# AMP.net
KiCad netlist of a schematic drawn in Altium Designer
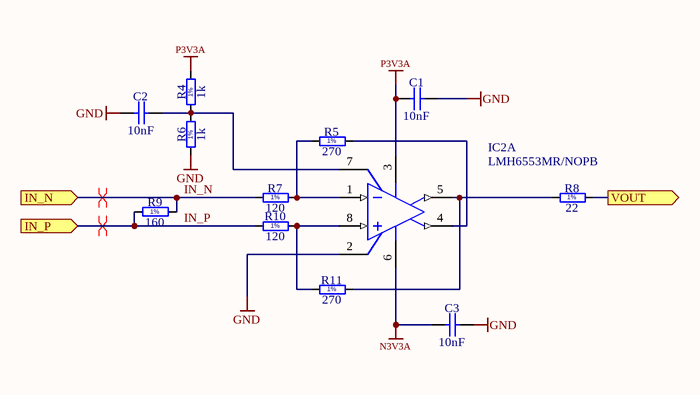
[diagram p0: AMP.SchDoc]

(export (version "E")
  (design (tool "Eeschema 10.0.6"))
  (components
    (comp (ref "C1")
      (value "10nF")
      (footprint "CAPC1608X87N")
      (description "Non-polarised capacitor")
      (fields
        (field (name "PART NUMBER") "CC0603_10NF_50V_10%_X7R")
        (field (name "VOLTAGE") "50V")
        (field (name "AUTHOR") "CERN DEM JLC")
      )
      (libsource (lib "Capacitors") (part "Capacitor - non polarized"))
    )
    (comp (ref "C2")
      (value "10nF")
      (footprint "CAPC1608X87N")
      (description "Non-polarised capacitor")
      (fields
        (field (name "PART NUMBER") "CC0603_10NF_50V_10%_X7R")
        (field (name "VOLTAGE") "50V")
        (field (name "AUTHOR") "CERN DEM JLC")
      )
      (libsource (lib "Capacitors") (part "Capacitor - non polarized"))
    )
    (comp (ref "C3")
      (value "10nF")
      (footprint "CAPC1608X87N")
      (description "Non-polarised capacitor")
      (fields
        (field (name "PART NUMBER") "CC0603_10NF_50V_10%_X7R")
        (field (name "VOLTAGE") "50V")
        (field (name "AUTHOR") "CERN DEM JLC")
      )
      (libsource (lib "Capacitors") (part "Capacitor - non polarized"))
    )
    (comp (ref "IC2")
      (value "LMH6553MR/NOPB")
      (footprint "DDA0008D_M")
      (description "900 MHz Fully Differential Amplifier with Output Limiting Clamp, 8-pin PSOP, Pb-Free")
      (fields (field (name "MANUFACTURER") "Texas Instruments"))
      (libsource (lib "Altium Content Vault") (part "AMP-DIFA-LMH6553-9"))
    )
    (comp (ref "R4")
      (value "1k")
      (footprint "RESC1608X55N")
      (description "Resistor - 1%")
      (fields
        (field (name "PART NUMBER") "R0603_1K_1%_0.1W_100PPM")
        (field (name "POWER") "0.1W")
        (field (name "AUTHOR") "CERN DEM JLC")
      )
      (libsource (lib "Resistors") (part "Resistor - 1%"))
    )
    (comp (ref "R5")
      (value "270")
      (footprint "RESC1608X55N")
      (description "Resistor - 1%")
      (fields
        (field (name "PART NUMBER") "R0603_270R_1%_0.1W_100PPM")
        (field (name "POWER") "0.1W")
        (field (name "AUTHOR") "CERN DEM JLC")
      )
      (libsource (lib "Resistors") (part "Resistor - 1%"))
    )
    (comp (ref "R6")
      (value "1k")
      (footprint "RESC1608X55N")
      (description "Resistor - 1%")
      (fields
        (field (name "PART NUMBER") "R0603_1K_1%_0.1W_100PPM")
        (field (name "POWER") "0.1W")
        (field (name "AUTHOR") "CERN DEM JLC")
      )
      (libsource (lib "Resistors") (part "Resistor - 1%"))
    )
    (comp (ref "R7")
      (value "120")
      (footprint "RESC1608X55N")
      (description "Resistor - 1%")
      (fields
        (field (name "PART NUMBER") "R0603_120R_1%_0.1W_100PPM")
        (field (name "POWER") "0.1W")
        (field (name "AUTHOR") "CERN DEM JLC")
      )
      (libsource (lib "Resistors") (part "Resistor - 1%"))
    )
    (comp (ref "R8")
      (value "22")
      (footprint "RESC1608X55N")
      (description "Resistor - 1%")
      (fields
        (field (name "PART NUMBER") "R0603_22R_1%_0.1W_100PPM")
        (field (name "POWER") "0.1W")
        (field (name "AUTHOR") "CERN DEM JLC")
      )
      (libsource (lib "Resistors") (part "Resistor - 1%"))
    )
    (comp (ref "R9")
      (value "160")
      (footprint "RESC1608X55N")
      (description "Resistor - 1%")
      (fields
        (field (name "PART NUMBER") "R0603_160R_1%_0.1W_100PPM")
        (field (name "POWER") "0.1W")
        (field (name "AUTHOR") "CERN DEM JLC")
      )
      (libsource (lib "Resistors") (part "Resistor - 1%"))
    )
    (comp (ref "R10")
      (value "120")
      (footprint "RESC1608X55N")
      (description "Resistor - 1%")
      (fields
        (field (name "PART NUMBER") "R0603_120R_1%_0.1W_100PPM")
        (field (name "POWER") "0.1W")
        (field (name "AUTHOR") "CERN DEM JLC")
      )
      (libsource (lib "Resistors") (part "Resistor - 1%"))
    )
    (comp (ref "R11")
      (value "270")
      (footprint "RESC1608X55N")
      (description "Resistor - 1%")
      (fields
        (field (name "PART NUMBER") "R0603_270R_1%_0.1W_100PPM")
        (field (name "POWER") "0.1W")
        (field (name "AUTHOR") "CERN DEM JLC")
      )
      (libsource (lib "Resistors") (part "Resistor - 1%"))
    )
  )
  (nets
    (net (code "1") (name "/IN_N") (class "Default")
      (node (ref "R7") (pin "1") (pinfunction "1_1") (pintype "passive"))
      (node (ref "R9") (pin "2") (pinfunction "2_2") (pintype "passive"))
    )
    (net (code "2") (name "/IN_P") (class "Default")
      (node (ref "R10") (pin "1") (pinfunction "1_1") (pintype "passive"))
      (node (ref "R9") (pin "1") (pinfunction "1_1") (pintype "passive"))
    )
    (net (code "3") (name "/VOUT") (class "Default")
      (node (ref "R8") (pin "2") (pinfunction "2_2") (pintype "passive"))
    )
    (net (code "4") (name "GND") (class "Default")
      (node (ref "C1") (pin "2") (pinfunction "2_2") (pintype "passive"))
      (node (ref "C2") (pin "1") (pinfunction "1_1") (pintype "passive"))
      (node (ref "C3") (pin "2") (pinfunction "2_2") (pintype "passive"))
      (node (ref "IC2") (pin "2") (pinfunction "VCM_2") (pintype "passive"))
      (node (ref "R6") (pin "1") (pinfunction "1_1") (pintype "passive"))
    )
    (net (code "5") (name "N3V3A") (class "Default")
      (node (ref "C3") (pin "1") (pinfunction "1_1") (pintype "passive"))
      (node (ref "IC2") (pin "6") (pinfunction "V-_6") (pintype "power_in"))
    )
    (net (code "6") (name "Net-(IC2A-IN+)") (class "Default")
      (node (ref "IC2") (pin "8") (pinfunction "IN+_8") (pintype "input"))
      (node (ref "R10") (pin "2") (pinfunction "2_2") (pintype "passive"))
      (node (ref "R11") (pin "1") (pinfunction "1_1") (pintype "passive"))
    )
    (net (code "7") (name "Net-(IC2A-IN-)") (class "Default")
      (node (ref "IC2") (pin "1") (pinfunction "IN-_1") (pintype "input"))
      (node (ref "R5") (pin "1") (pinfunction "1_1") (pintype "passive"))
      (node (ref "R7") (pin "2") (pinfunction "2_2") (pintype "passive"))
    )
    (net (code "8") (name "Net-(IC2A-OUT+)") (class "Default")
      (node (ref "IC2") (pin "4") (pinfunction "OUT+_4") (pintype "output"))
      (node (ref "R5") (pin "2") (pinfunction "2_2") (pintype "passive"))
    )
    (net (code "9") (name "Net-(IC2A-OUT-)") (class "Default")
      (node (ref "IC2") (pin "5") (pinfunction "OUT-_5") (pintype "output"))
      (node (ref "R11") (pin "2") (pinfunction "2_2") (pintype "passive"))
      (node (ref "R8") (pin "1") (pinfunction "1_1") (pintype "passive"))
    )
    (net (code "10") (name "Net-(IC2A-VCLAMP)") (class "Default")
      (node (ref "C2") (pin "2") (pinfunction "2_2") (pintype "passive"))
      (node (ref "IC2") (pin "7") (pinfunction "VCLAMP_7") (pintype "passive"))
      (node (ref "R4") (pin "1") (pinfunction "1_1") (pintype "passive"))
      (node (ref "R6") (pin "2") (pinfunction "2_2") (pintype "passive"))
    )
    (net (code "11") (name "P3V3A") (class "Default")
      (node (ref "C1") (pin "1") (pinfunction "1_1") (pintype "passive"))
      (node (ref "IC2") (pin "3") (pinfunction "V+_3") (pintype "power_in"))
      (node (ref "R4") (pin "2") (pinfunction "2_2") (pintype "passive"))
    )
  )
)
